# USB.net
KiCad netlist of a schematic drawn in Altium Designer
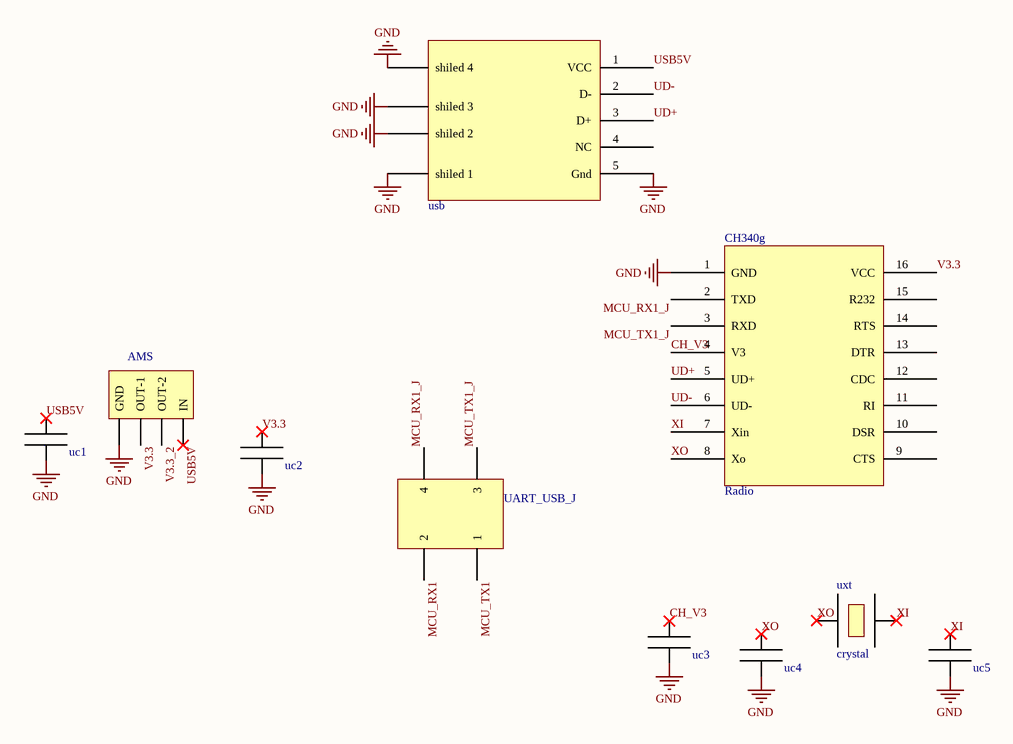
[diagram p0: USB.SchDoc]

(export (version "E")
  (design (tool "Eeschema 10.0.6"))
  (components
    (comp (ref "AMS")
      (value "Regulator")
      (footprint "abr_fp_SOT-223_3d")
      (libsource (lib "abr_reg_smd-96-04") (part "abr_reg_AMS1117"))
    )
    (comp (ref "CH340g")
      (value "Radio")
      (footprint "abr_usb_ch344g_3d")
      (libsource (lib "lible") (part "abr_usb_ch340g"))
    )
    (comp (ref "UART_USB_J")
      (value "pin header 2mm")
      (footprint "abr_ph_2x2_2mm_3d_male")
      (libsource (lib "abr_ph_2mm_96_02") (part "abr_2x2_2mm"))
    )
    (comp (ref "uc1")
      (value "1uf")
      (footprint "abr_cap_0805_3d")
      (libsource (lib "abr_smd_0805_all") (part "abr_cap_0805"))
    )
    (comp (ref "uc2")
      (value "1uf")
      (footprint "abr_cap_0805_3d")
      (libsource (lib "abr_smd_0805_all") (part "abr_cap_0805"))
    )
    (comp (ref "uc3")
      (value "100nf")
      (footprint "abr_cap_0805_3d")
      (libsource (lib "abr_smd_0805_all") (part "abr_cap_0805"))
    )
    (comp (ref "uc4")
      (value "22pf")
      (footprint "abr_cap_0805_3d")
      (libsource (lib "abr_smd_0805_all") (part "abr_cap_0805"))
    )
    (comp (ref "uc5")
      (value "22pf")
      (footprint "abr_cap_0805_3d")
      (libsource (lib "abr_smd_0805_all") (part "abr_cap_0805"))
    )
    (comp (ref "usb")
      (value "usb connector")
      (footprint "abr_usb_micro_hoawey_p6_3d")
      (libsource (lib "usb_related_96_02") (part "abr_usb_micro_female"))
    )
    (comp (ref "uxt")
      (value "crystal")
      (footprint "abr_crystal_dip_3d")
      (libsource (lib "abr_crystal_osc_96_02") (part "abr_crystal"))
    )
  )
  (nets
    (net (code "1") (name "/CH_V3") (class "Default")
      (node (ref "CH340g") (pin "4") (pinfunction "V3_4") (pintype "passive"))
      (node (ref "uc3") (pin "1") (pinfunction "10_1") (pintype "passive"))
    )
    (net (code "2") (name "/MCU_RX1") (class "Default")
      (node (ref "UART_USB_J") (pin "2") (pinfunction "2_2") (pintype "passive"))
    )
    (net (code "3") (name "/MCU_RX1_J") (class "Default")
      (node (ref "CH340g") (pin "2") (pinfunction "TXD_2") (pintype "passive"))
      (node (ref "UART_USB_J") (pin "4") (pinfunction "4_4") (pintype "passive"))
    )
    (net (code "4") (name "/MCU_TX1") (class "Default")
      (node (ref "UART_USB_J") (pin "1") (pinfunction "1_1") (pintype "passive"))
    )
    (net (code "5") (name "/MCU_TX1_J") (class "Default")
      (node (ref "CH340g") (pin "3") (pinfunction "RXD_3") (pintype "passive"))
      (node (ref "UART_USB_J") (pin "3") (pinfunction "3_3") (pintype "passive"))
    )
    (net (code "6") (name "/UD+") (class "Default")
      (node (ref "CH340g") (pin "5") (pinfunction "UD+_5") (pintype "passive"))
      (node (ref "usb") (pin "3") (pinfunction "D+_3") (pintype "passive"))
    )
    (net (code "7") (name "/UD-") (class "Default")
      (node (ref "CH340g") (pin "6") (pinfunction "UD-_6") (pintype "passive"))
      (node (ref "usb") (pin "2") (pinfunction "D-_2") (pintype "passive"))
    )
    (net (code "8") (name "/USB5V") (class "Default")
      (node (ref "AMS") (pin "3") (pinfunction "IN_3") (pintype "passive"))
      (node (ref "uc1") (pin "1") (pinfunction "10_1") (pintype "passive"))
      (node (ref "usb") (pin "1") (pinfunction "VCC_1") (pintype "passive"))
    )
    (net (code "9") (name "/V3.3") (class "Default")
      (node (ref "AMS") (pin "2") (pinfunction "OUT-1_2") (pintype "passive"))
      (node (ref "CH340g") (pin "16") (pinfunction "VCC_16") (pintype "passive"))
      (node (ref "uc2") (pin "1") (pinfunction "10_1") (pintype "passive"))
    )
    (net (code "10") (name "/V3.3_2") (class "Default")
      (node (ref "AMS") (pin "4") (pinfunction "OUT-2_4") (pintype "passive"))
    )
    (net (code "11") (name "/XI") (class "Default")
      (node (ref "CH340g") (pin "7") (pinfunction "Xin_7") (pintype "passive"))
      (node (ref "uc5") (pin "1") (pinfunction "10_1") (pintype "passive"))
      (node (ref "uxt") (pin "2") (pintype "passive"))
    )
    (net (code "12") (name "/XO") (class "Default")
      (node (ref "CH340g") (pin "8") (pinfunction "Xo_8") (pintype "passive"))
      (node (ref "uc4") (pin "1") (pinfunction "10_1") (pintype "passive"))
      (node (ref "uxt") (pin "1") (pintype "passive"))
    )
    (net (code "13") (name "GND") (class "Default")
      (node (ref "AMS") (pin "1") (pinfunction "GND_1") (pintype "passive"))
      (node (ref "CH340g") (pin "1") (pinfunction "GND_1") (pintype "passive"))
      (node (ref "uc1") (pin "0") (pinfunction "2_0") (pintype "passive"))
      (node (ref "uc2") (pin "0") (pinfunction "2_0") (pintype "passive"))
      (node (ref "uc3") (pin "0") (pinfunction "2_0") (pintype "passive"))
      (node (ref "uc4") (pin "0") (pinfunction "2_0") (pintype "passive"))
      (node (ref "uc5") (pin "0") (pinfunction "2_0") (pintype "passive"))
      (node (ref "usb") (pin "5") (pinfunction "Gnd_5") (pintype "passive"))
      (node (ref "usb") (pin "6") (pinfunction "shiled_1_6") (pintype "passive"))
      (node (ref "usb") (pin "7") (pinfunction "shiled_2_7") (pintype "passive"))
      (node (ref "usb") (pin "8") (pinfunction "shiled_3_8") (pintype "passive"))
      (node (ref "usb") (pin "9") (pinfunction "shiled_4_9") (pintype "passive"))
    )
    (net (code "14") (name "unconnected-(CH340g-CDC-Pad12)") (class "Default")
      (node (ref "CH340g") (pin "12") (pinfunction "CDC_12") (pintype "passive"))
    )
    (net (code "15") (name "unconnected-(CH340g-CTS-Pad9)") (class "Default")
      (node (ref "CH340g") (pin "9") (pinfunction "CTS_9") (pintype "passive"))
    )
    (net (code "16") (name "unconnected-(CH340g-DSR-Pad10)") (class "Default")
      (node (ref "CH340g") (pin "10") (pinfunction "DSR_10") (pintype "passive"))
    )
    (net (code "17") (name "unconnected-(CH340g-DTR-Pad13)") (class "Default")
      (node (ref "CH340g") (pin "13") (pinfunction "DTR_13") (pintype "passive"))
    )
    (net (code "18") (name "unconnected-(CH340g-R232-Pad15)") (class "Default")
      (node (ref "CH340g") (pin "15") (pinfunction "R232_15") (pintype "passive"))
    )
    (net (code "19") (name "unconnected-(CH340g-RI-Pad11)") (class "Default")
      (node (ref "CH340g") (pin "11") (pinfunction "RI_11") (pintype "passive"))
    )
    (net (code "20") (name "unconnected-(CH340g-RTS-Pad14)") (class "Default")
      (node (ref "CH340g") (pin "14") (pinfunction "RTS_14") (pintype "passive"))
    )
    (net (code "21") (name "unconnected-(usb-NC-Pad4)") (class "Default")
      (node (ref "usb") (pin "4") (pinfunction "NC_4") (pintype "passive"))
    )
  )
)
